# FanControl.net
KiCad netlist of a schematic drawn in Altium Designer
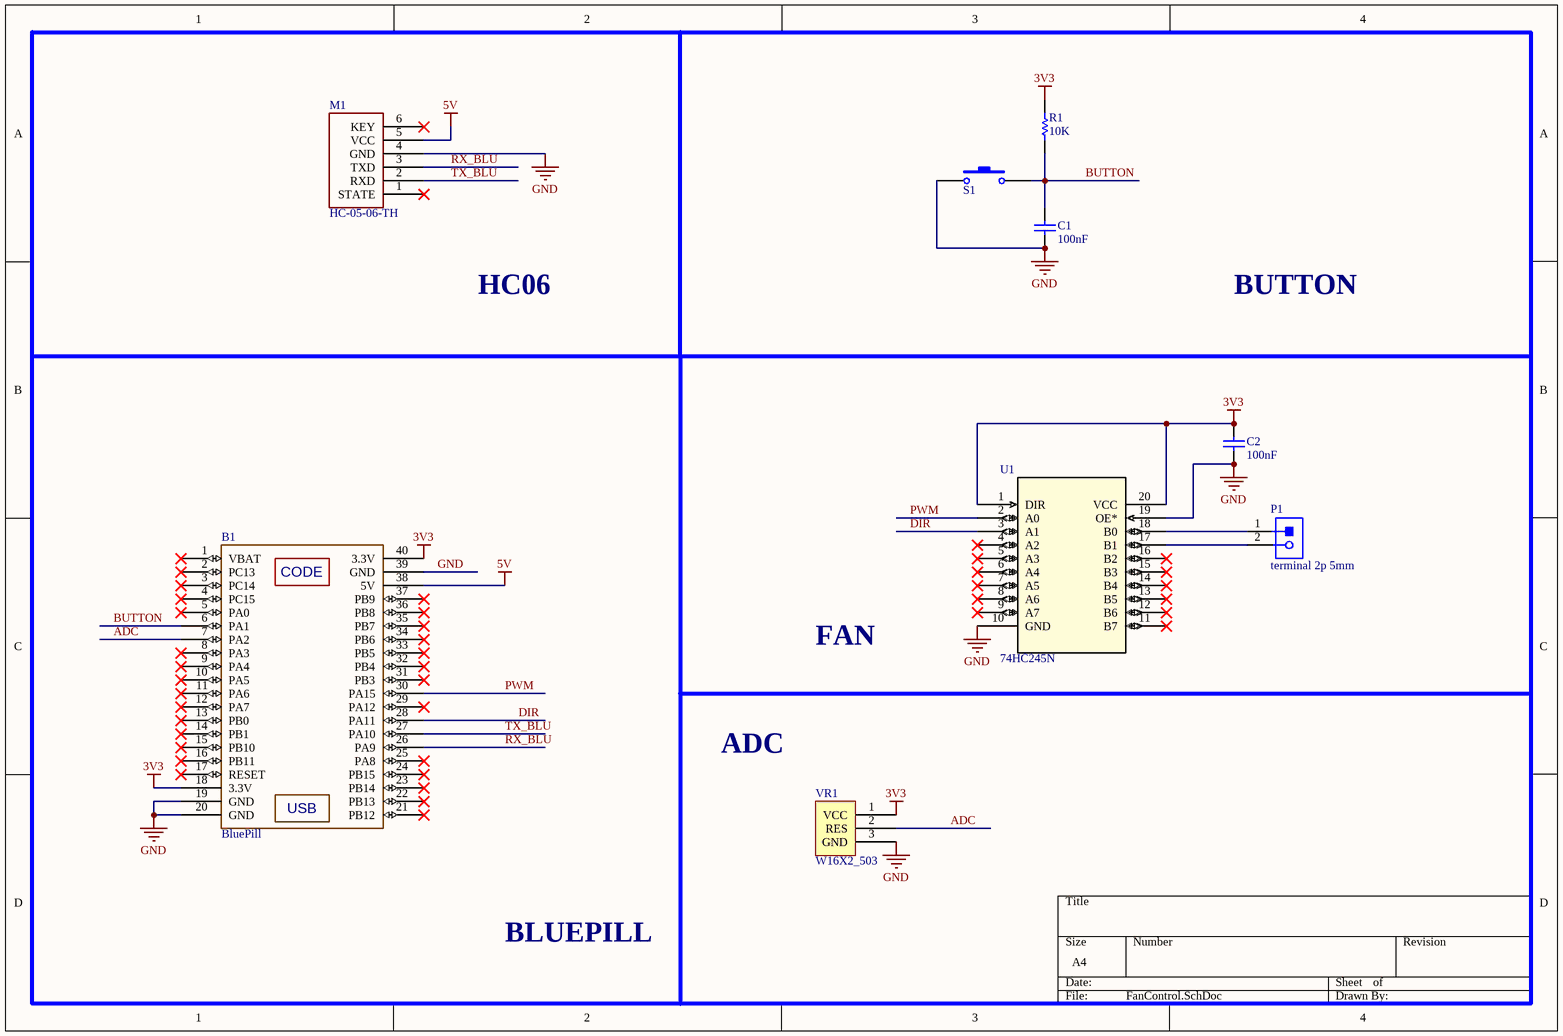
[diagram p0: FanControl.SchDoc]

(export (version "E")
  (design (tool "Eeschema 10.0.6"))
  (components
    (comp (ref "B1")
      (value "BluePill")
      (footprint "BlUEPILL")
      (libsource (lib "dev-board") (part "BluePill"))
    )
    (comp (ref "C1")
      (value "100nF")
      (footprint "CAP-SM-0805")
      (description "Capacitor")
      (fields (field (name "Comment") "Cap Non-Pol SMD"))
      (libsource (lib "PIF_Library") (part "Cap Non-Pol SMD"))
    )
    (comp (ref "C2")
      (value "100nF")
      (footprint "CAP-SM-0805")
      (description "Capacitor")
      (fields (field (name "Comment") "Cap Non-Pol SMD"))
      (libsource (lib "PIF_Library") (part "Cap Non-Pol SMD"))
    )
    (comp (ref "M1")
      (value "HC-05-06-TH")
      (footprint "HC-05-06-TH")
      (libsource (lib "PIFWRobot") (part "HC-05-06-TH"))
    )
    (comp (ref "P1")
      (value "terminal 2p 5mm")
      (footprint "terminal 2p 5mm")
      (libsource (lib "CNCMicaMini") (part "terminal 2p 5mm"))
    )
    (comp (ref "R1")
      (value "10K")
      (footprint "RES-SM-0603")
      (description "Resistor")
      (fields (field (name "Comment") "RESISTOR SMD"))
      (libsource (lib "PIF_Library") (part "RESISTOR SMD"))
    )
    (comp (ref "S1")
      (value "Tact SW - 2Pin")
      (footprint "SW2")
      (description "Switch button 2 pin")
      (libsource (lib "PIF_Library") (part "Tact SW - 2Pin"))
    )
    (comp (ref "U1")
      (value "74HC245N")
      (footprint "74HC245N")
      (description "No Description Available")
      (fields (field (name "COPYRIGHT") "Copyright (C) 2022 Ultra Librarian. All rights reserved."))
      (libsource (lib "CNCMicaMini") (part "74HC245N"))
    )
    (comp (ref "VR1")
      (value "W16X2_503")
      (footprint "W16X2_503")
      (libsource (lib "CNCMicaMini") (part "W16X2_503"))
    )
  )
  (nets
    (net (code "1") (name "/ADC") (class "Default")
      (node (ref "B1") (pin "7") (pinfunction "PA2_7") (pintype "bidirectional"))
      (node (ref "VR1") (pin "2") (pinfunction "RES_2") (pintype "passive"))
    )
    (net (code "2") (name "/BUTTON") (class "Default")
      (node (ref "B1") (pin "6") (pinfunction "PA1_6") (pintype "bidirectional"))
      (node (ref "C1") (pin "2") (pinfunction "2_2") (pintype "passive"))
      (node (ref "R1") (pin "1") (pinfunction "1_1") (pintype "passive"))
      (node (ref "S1") (pin "2") (pinfunction "2_2") (pintype "passive"))
    )
    (net (code "3") (name "/DIR") (class "Default")
      (node (ref "B1") (pin "28") (pinfunction "PA11_28") (pintype "bidirectional"))
      (node (ref "U1") (pin "3") (pinfunction "A1_3") (pintype "bidirectional"))
    )
    (net (code "4") (name "/PWM") (class "Default")
      (node (ref "B1") (pin "30") (pinfunction "PA15_30") (pintype "bidirectional"))
      (node (ref "U1") (pin "2") (pinfunction "A0_2") (pintype "bidirectional"))
    )
    (net (code "5") (name "/RX_BLU") (class "Default")
      (node (ref "B1") (pin "26") (pinfunction "PA9_26") (pintype "bidirectional"))
      (node (ref "M1") (pin "3") (pinfunction "TXD_3") (pintype "passive"))
    )
    (net (code "6") (name "/TX_BLU") (class "Default")
      (node (ref "B1") (pin "27") (pinfunction "PA10_27") (pintype "bidirectional"))
      (node (ref "M1") (pin "2") (pinfunction "RXD_2") (pintype "passive"))
    )
    (net (code "7") (name "3V3") (class "Default")
      (node (ref "B1") (pin "18") (pinfunction "3.3V_18") (pintype "power_in"))
      (node (ref "B1") (pin "40") (pinfunction "3.3V_40") (pintype "power_in"))
      (node (ref "C2") (pin "2") (pinfunction "2_2") (pintype "passive"))
      (node (ref "R1") (pin "2") (pinfunction "2_2") (pintype "passive"))
      (node (ref "U1") (pin "1") (pinfunction "DIR_1") (pintype "input"))
      (node (ref "U1") (pin "20") (pinfunction "VCC_20") (pintype "power_in"))
      (node (ref "VR1") (pin "1") (pinfunction "VCC_1") (pintype "passive"))
    )
    (net (code "8") (name "5V") (class "Default")
      (node (ref "B1") (pin "38") (pinfunction "5V_38") (pintype "power_in"))
      (node (ref "M1") (pin "5") (pinfunction "VCC_5") (pintype "passive"))
    )
    (net (code "9") (name "GND") (class "Default")
      (node (ref "B1") (pin "19") (pinfunction "GND_19") (pintype "power_in"))
      (node (ref "B1") (pin "20") (pinfunction "GND_20") (pintype "power_in"))
      (node (ref "B1") (pin "39") (pinfunction "GND_39") (pintype "power_in"))
      (node (ref "C1") (pin "1") (pinfunction "1_1") (pintype "passive"))
      (node (ref "C2") (pin "1") (pinfunction "1_1") (pintype "passive"))
      (node (ref "M1") (pin "4") (pinfunction "GND_4") (pintype "passive"))
      (node (ref "S1") (pin "1") (pinfunction "1_1") (pintype "passive"))
      (node (ref "U1") (pin "10") (pinfunction "GND_10") (pintype "power_in"))
      (node (ref "U1") (pin "19") (pinfunction "OE*_19") (pintype "input"))
      (node (ref "VR1") (pin "3") (pinfunction "GND_3") (pintype "passive"))
    )
    (net (code "10") (name "Net-(U1-B0)") (class "Default")
      (node (ref "P1") (pin "1") (pinfunction "1_1") (pintype "passive"))
      (node (ref "U1") (pin "18") (pinfunction "B0_18") (pintype "bidirectional"))
    )
    (net (code "11") (name "Net-(U1-B1)") (class "Default")
      (node (ref "P1") (pin "2") (pinfunction "1_2") (pintype "passive"))
      (node (ref "U1") (pin "17") (pinfunction "B1_17") (pintype "bidirectional"))
    )
    (net (code "12") (name "unconnected-(B1-PA0-Pad5)") (class "Default")
      (node (ref "B1") (pin "5") (pinfunction "PA0_5") (pintype "bidirectional+no_connect"))
    )
    (net (code "13") (name "unconnected-(B1-PA3-Pad8)") (class "Default")
      (node (ref "B1") (pin "8") (pinfunction "PA3_8") (pintype "bidirectional+no_connect"))
    )
    (net (code "14") (name "unconnected-(B1-PA4-Pad9)") (class "Default")
      (node (ref "B1") (pin "9") (pinfunction "PA4_9") (pintype "bidirectional+no_connect"))
    )
    (net (code "15") (name "unconnected-(B1-PA5-Pad10)") (class "Default")
      (node (ref "B1") (pin "10") (pinfunction "PA5_10") (pintype "bidirectional+no_connect"))
    )
    (net (code "16") (name "unconnected-(B1-PA6-Pad11)") (class "Default")
      (node (ref "B1") (pin "11") (pinfunction "PA6_11") (pintype "bidirectional+no_connect"))
    )
    (net (code "17") (name "unconnected-(B1-PA7-Pad12)") (class "Default")
      (node (ref "B1") (pin "12") (pinfunction "PA7_12") (pintype "bidirectional+no_connect"))
    )
    (net (code "18") (name "unconnected-(B1-PA8-Pad25)") (class "Default")
      (node (ref "B1") (pin "25") (pinfunction "PA8_25") (pintype "bidirectional+no_connect"))
    )
    (net (code "19") (name "unconnected-(B1-PA12-Pad29)") (class "Default")
      (node (ref "B1") (pin "29") (pinfunction "PA12_29") (pintype "bidirectional+no_connect"))
    )
    (net (code "20") (name "unconnected-(B1-PB0-Pad13)") (class "Default")
      (node (ref "B1") (pin "13") (pinfunction "PB0_13") (pintype "bidirectional+no_connect"))
    )
    (net (code "21") (name "unconnected-(B1-PB1-Pad14)") (class "Default")
      (node (ref "B1") (pin "14") (pinfunction "PB1_14") (pintype "bidirectional+no_connect"))
    )
    (net (code "22") (name "unconnected-(B1-PB3-Pad31)") (class "Default")
      (node (ref "B1") (pin "31") (pinfunction "PB3_31") (pintype "bidirectional+no_connect"))
    )
    (net (code "23") (name "unconnected-(B1-PB4-Pad32)") (class "Default")
      (node (ref "B1") (pin "32") (pinfunction "PB4_32") (pintype "bidirectional+no_connect"))
    )
    (net (code "24") (name "unconnected-(B1-PB5-Pad33)") (class "Default")
      (node (ref "B1") (pin "33") (pinfunction "PB5_33") (pintype "bidirectional+no_connect"))
    )
    (net (code "25") (name "unconnected-(B1-PB6-Pad34)") (class "Default")
      (node (ref "B1") (pin "34") (pinfunction "PB6_34") (pintype "bidirectional+no_connect"))
    )
    (net (code "26") (name "unconnected-(B1-PB7-Pad35)") (class "Default")
      (node (ref "B1") (pin "35") (pinfunction "PB7_35") (pintype "bidirectional+no_connect"))
    )
    (net (code "27") (name "unconnected-(B1-PB8-Pad36)") (class "Default")
      (node (ref "B1") (pin "36") (pinfunction "PB8_36") (pintype "bidirectional+no_connect"))
    )
    (net (code "28") (name "unconnected-(B1-PB9-Pad37)") (class "Default")
      (node (ref "B1") (pin "37") (pinfunction "PB9_37") (pintype "bidirectional+no_connect"))
    )
    (net (code "29") (name "unconnected-(B1-PB10-Pad15)") (class "Default")
      (node (ref "B1") (pin "15") (pinfunction "PB10_15") (pintype "bidirectional+no_connect"))
    )
    (net (code "30") (name "unconnected-(B1-PB11-Pad16)") (class "Default")
      (node (ref "B1") (pin "16") (pinfunction "PB11_16") (pintype "bidirectional+no_connect"))
    )
    (net (code "31") (name "unconnected-(B1-PB12-Pad21)") (class "Default")
      (node (ref "B1") (pin "21") (pinfunction "PB12_21") (pintype "bidirectional+no_connect"))
    )
    (net (code "32") (name "unconnected-(B1-PB13-Pad22)") (class "Default")
      (node (ref "B1") (pin "22") (pinfunction "PB13_22") (pintype "bidirectional+no_connect"))
    )
    (net (code "33") (name "unconnected-(B1-PB14-Pad23)") (class "Default")
      (node (ref "B1") (pin "23") (pinfunction "PB14_23") (pintype "bidirectional+no_connect"))
    )
    (net (code "34") (name "unconnected-(B1-PB15-Pad24)") (class "Default")
      (node (ref "B1") (pin "24") (pinfunction "PB15_24") (pintype "bidirectional+no_connect"))
    )
    (net (code "35") (name "unconnected-(B1-PC13-Pad2)") (class "Default")
      (node (ref "B1") (pin "2") (pinfunction "PC13_2") (pintype "bidirectional+no_connect"))
    )
    (net (code "36") (name "unconnected-(B1-PC14-Pad3)") (class "Default")
      (node (ref "B1") (pin "3") (pinfunction "PC14_3") (pintype "bidirectional+no_connect"))
    )
    (net (code "37") (name "unconnected-(B1-PC15-Pad4)") (class "Default")
      (node (ref "B1") (pin "4") (pinfunction "PC15_4") (pintype "bidirectional+no_connect"))
    )
    (net (code "38") (name "unconnected-(B1-RESET-Pad17)") (class "Default")
      (node (ref "B1") (pin "17") (pinfunction "RESET_17") (pintype "bidirectional+no_connect"))
    )
    (net (code "39") (name "unconnected-(B1-VBAT-Pad1)") (class "Default")
      (node (ref "B1") (pin "1") (pinfunction "VBAT_1") (pintype "bidirectional+no_connect"))
    )
    (net (code "40") (name "unconnected-(M1-KEY-Pad6)") (class "Default")
      (node (ref "M1") (pin "6") (pinfunction "KEY_6") (pintype "passive+no_connect"))
    )
    (net (code "41") (name "unconnected-(M1-STATE-Pad1)") (class "Default")
      (node (ref "M1") (pin "1") (pinfunction "STATE_1") (pintype "passive+no_connect"))
    )
    (net (code "42") (name "unconnected-(U1-A2-Pad4)") (class "Default")
      (node (ref "U1") (pin "4") (pinfunction "A2_4") (pintype "bidirectional+no_connect"))
    )
    (net (code "43") (name "unconnected-(U1-A3-Pad5)") (class "Default")
      (node (ref "U1") (pin "5") (pinfunction "A3_5") (pintype "bidirectional+no_connect"))
    )
    (net (code "44") (name "unconnected-(U1-A4-Pad6)") (class "Default")
      (node (ref "U1") (pin "6") (pinfunction "A4_6") (pintype "bidirectional+no_connect"))
    )
    (net (code "45") (name "unconnected-(U1-A5-Pad7)") (class "Default")
      (node (ref "U1") (pin "7") (pinfunction "A5_7") (pintype "bidirectional+no_connect"))
    )
    (net (code "46") (name "unconnected-(U1-A6-Pad8)") (class "Default")
      (node (ref "U1") (pin "8") (pinfunction "A6_8") (pintype "bidirectional+no_connect"))
    )
    (net (code "47") (name "unconnected-(U1-A7-Pad9)") (class "Default")
      (node (ref "U1") (pin "9") (pinfunction "A7_9") (pintype "bidirectional+no_connect"))
    )
    (net (code "48") (name "unconnected-(U1-B2-Pad16)") (class "Default")
      (node (ref "U1") (pin "16") (pinfunction "B2_16") (pintype "bidirectional+no_connect"))
    )
    (net (code "49") (name "unconnected-(U1-B3-Pad15)") (class "Default")
      (node (ref "U1") (pin "15") (pinfunction "B3_15") (pintype "bidirectional+no_connect"))
    )
    (net (code "50") (name "unconnected-(U1-B4-Pad14)") (class "Default")
      (node (ref "U1") (pin "14") (pinfunction "B4_14") (pintype "bidirectional+no_connect"))
    )
    (net (code "51") (name "unconnected-(U1-B5-Pad13)") (class "Default")
      (node (ref "U1") (pin "13") (pinfunction "B5_13") (pintype "bidirectional+no_connect"))
    )
    (net (code "52") (name "unconnected-(U1-B6-Pad12)") (class "Default")
      (node (ref "U1") (pin "12") (pinfunction "B6_12") (pintype "bidirectional+no_connect"))
    )
    (net (code "53") (name "unconnected-(U1-B7-Pad11)") (class "Default")
      (node (ref "U1") (pin "11") (pinfunction "B7_11") (pintype "bidirectional+no_connect"))
    )
  )
)
